# GloveControl_Module_20200316_0.net
KiCad netlist of a schematic drawn in EAGLE
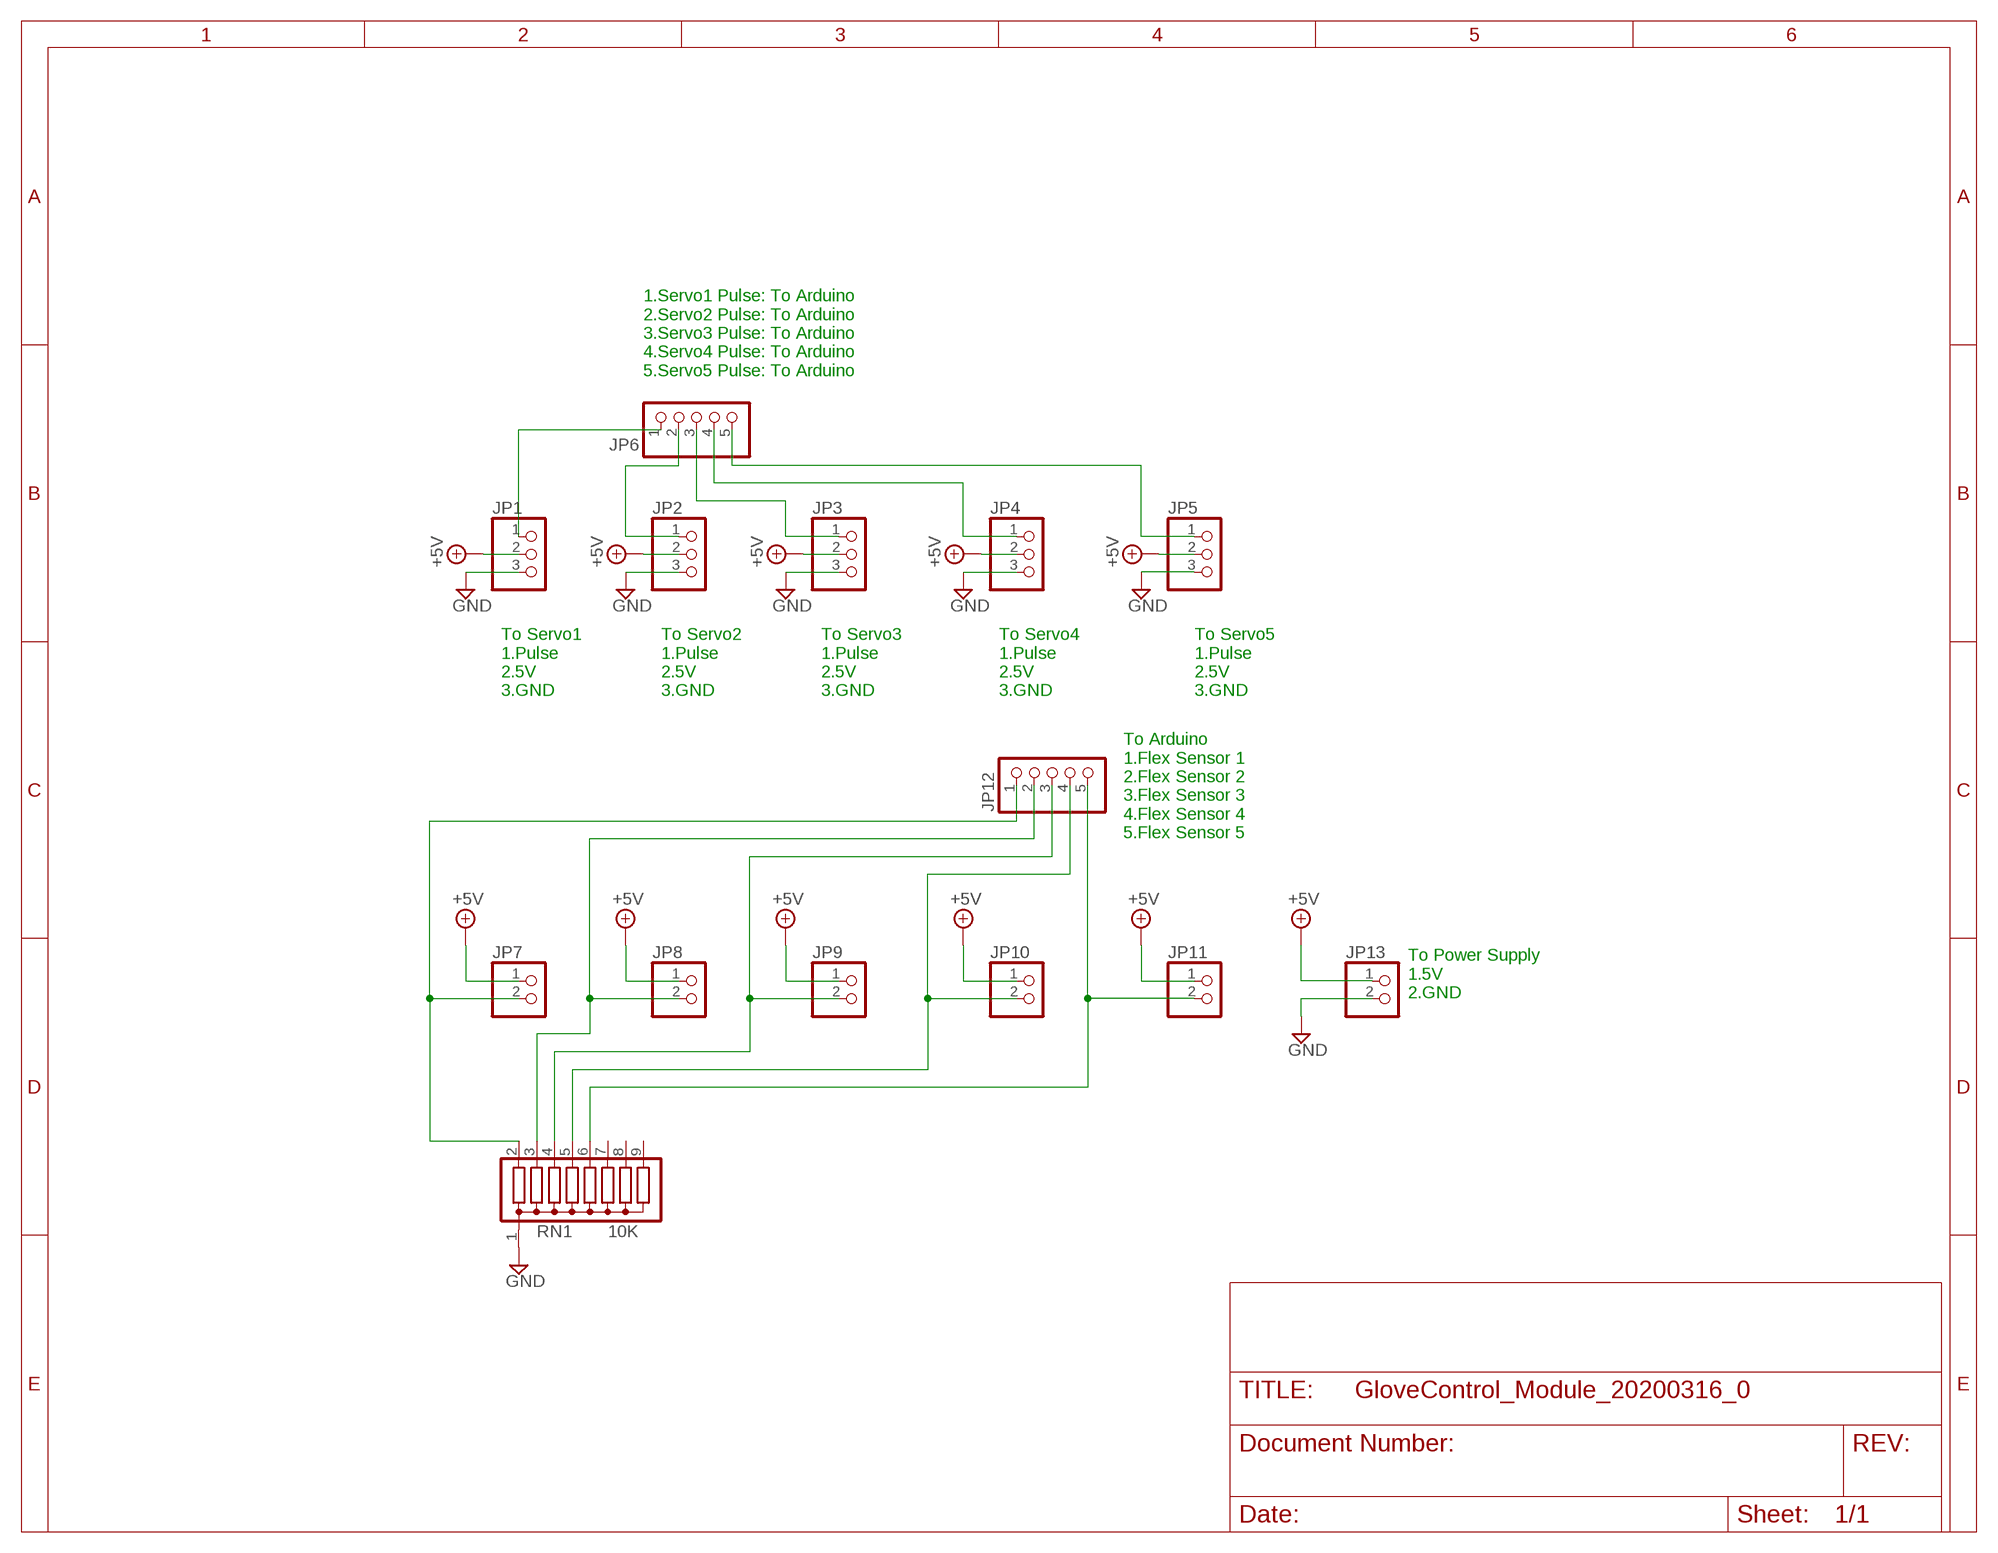
[diagram p0: schematic, sheet 1]

(export (version "E")
  (design (tool "Eeschema 10.0.6"))
  (components
    (comp (ref "JP1")
      (value "PINHD-1X3")
      (footprint "eagle-import:1X03")
      (libsource (lib "eagle-import") (part "PINHD-1X3"))
    )
    (comp (ref "JP2")
      (value "PINHD-1X3")
      (footprint "eagle-import:1X03")
      (libsource (lib "eagle-import") (part "PINHD-1X3"))
    )
    (comp (ref "JP3")
      (value "PINHD-1X3")
      (footprint "eagle-import:1X03")
      (libsource (lib "eagle-import") (part "PINHD-1X3"))
    )
    (comp (ref "JP4")
      (value "PINHD-1X3")
      (footprint "eagle-import:1X03")
      (libsource (lib "eagle-import") (part "PINHD-1X3"))
    )
    (comp (ref "JP5")
      (value "PINHD-1X3")
      (footprint "eagle-import:1X03")
      (libsource (lib "eagle-import") (part "PINHD-1X3"))
    )
    (comp (ref "JP6")
      (value "PINHD-1X5")
      (footprint "eagle-import:1X05")
      (libsource (lib "eagle-import") (part "PINHD-1X5"))
    )
    (comp (ref "JP7")
      (value "PINHD-1X2")
      (footprint "eagle-import:1X02")
      (libsource (lib "eagle-import") (part "PINHD-1X2"))
    )
    (comp (ref "JP8")
      (value "PINHD-1X2")
      (footprint "eagle-import:1X02")
      (libsource (lib "eagle-import") (part "PINHD-1X2"))
    )
    (comp (ref "JP9")
      (value "PINHD-1X2")
      (footprint "eagle-import:1X02")
      (libsource (lib "eagle-import") (part "PINHD-1X2"))
    )
    (comp (ref "JP10")
      (value "PINHD-1X2")
      (footprint "eagle-import:1X02")
      (libsource (lib "eagle-import") (part "PINHD-1X2"))
    )
    (comp (ref "JP11")
      (value "PINHD-1X2")
      (footprint "eagle-import:1X02")
      (libsource (lib "eagle-import") (part "PINHD-1X2"))
    )
    (comp (ref "JP12")
      (value "PINHD-1X5")
      (footprint "eagle-import:1X05")
      (libsource (lib "eagle-import") (part "PINHD-1X5"))
    )
    (comp (ref "JP13")
      (value "PINHD-1X2")
      (footprint "eagle-import:1X02")
      (libsource (lib "eagle-import") (part "PINHD-1X2"))
    )
    (comp (ref "RN1")
      (value "10K")
      (footprint "eagle-import:SIL9")
      (libsource (lib "eagle-import") (part "G08R"))
    )
  )
  (nets
    (net (code "1") (name "+5V") (class "Default")
      (node (ref "JP1") (pin "2") (pinfunction "2_2") (pintype "passive"))
      (node (ref "JP10") (pin "1") (pinfunction "1_1") (pintype "passive"))
      (node (ref "JP11") (pin "1") (pinfunction "1_1") (pintype "passive"))
      (node (ref "JP13") (pin "1") (pinfunction "1_1") (pintype "passive"))
      (node (ref "JP2") (pin "2") (pinfunction "2_2") (pintype "passive"))
      (node (ref "JP3") (pin "2") (pinfunction "2_2") (pintype "passive"))
      (node (ref "JP4") (pin "2") (pinfunction "2_2") (pintype "passive"))
      (node (ref "JP5") (pin "2") (pinfunction "2_2") (pintype "passive"))
      (node (ref "JP7") (pin "1") (pinfunction "1_1") (pintype "passive"))
      (node (ref "JP8") (pin "1") (pinfunction "1_1") (pintype "passive"))
      (node (ref "JP9") (pin "1") (pinfunction "1_1") (pintype "passive"))
    )
    (net (code "2") (name "GND") (class "Default")
      (node (ref "JP1") (pin "3") (pinfunction "3_3") (pintype "passive"))
      (node (ref "JP13") (pin "2") (pinfunction "2_2") (pintype "passive"))
      (node (ref "JP2") (pin "3") (pinfunction "3_3") (pintype "passive"))
      (node (ref "JP3") (pin "3") (pinfunction "3_3") (pintype "passive"))
      (node (ref "JP4") (pin "3") (pinfunction "3_3") (pintype "passive"))
      (node (ref "JP5") (pin "3") (pinfunction "3_3") (pintype "passive"))
      (node (ref "RN1") (pin "1") (pinfunction "1_1") (pintype "passive"))
    )
    (net (code "3") (name "Net-(JP1-Pad1)") (class "Default")
      (node (ref "JP1") (pin "1") (pinfunction "1_1") (pintype "passive"))
      (node (ref "JP6") (pin "1") (pinfunction "1_1") (pintype "passive"))
    )
    (net (code "4") (name "Net-(JP2-Pad1)") (class "Default")
      (node (ref "JP2") (pin "1") (pinfunction "1_1") (pintype "passive"))
      (node (ref "JP6") (pin "2") (pinfunction "2_2") (pintype "passive"))
    )
    (net (code "5") (name "Net-(JP3-Pad1)") (class "Default")
      (node (ref "JP3") (pin "1") (pinfunction "1_1") (pintype "passive"))
      (node (ref "JP6") (pin "3") (pinfunction "3_3") (pintype "passive"))
    )
    (net (code "6") (name "Net-(JP4-Pad1)") (class "Default")
      (node (ref "JP4") (pin "1") (pinfunction "1_1") (pintype "passive"))
      (node (ref "JP6") (pin "4") (pinfunction "4_4") (pintype "passive"))
    )
    (net (code "7") (name "Net-(JP5-Pad1)") (class "Default")
      (node (ref "JP5") (pin "1") (pinfunction "1_1") (pintype "passive"))
      (node (ref "JP6") (pin "5") (pinfunction "5_5") (pintype "passive"))
    )
    (net (code "8") (name "Net-(JP10-Pad2)") (class "Default")
      (node (ref "JP10") (pin "2") (pinfunction "2_2") (pintype "passive"))
      (node (ref "JP12") (pin "4") (pinfunction "4_4") (pintype "passive"))
      (node (ref "RN1") (pin "5") (pinfunction "5_5") (pintype "passive"))
    )
    (net (code "9") (name "Net-(JP11-Pad2)") (class "Default")
      (node (ref "JP11") (pin "2") (pinfunction "2_2") (pintype "passive"))
      (node (ref "JP12") (pin "5") (pinfunction "5_5") (pintype "passive"))
      (node (ref "RN1") (pin "6") (pinfunction "6_6") (pintype "passive"))
    )
    (net (code "10") (name "Net-(JP12-Pad1)") (class "Default")
      (node (ref "JP12") (pin "1") (pinfunction "1_1") (pintype "passive"))
      (node (ref "JP7") (pin "2") (pinfunction "2_2") (pintype "passive"))
      (node (ref "RN1") (pin "2") (pinfunction "2_2") (pintype "passive"))
    )
    (net (code "11") (name "Net-(JP12-Pad2)") (class "Default")
      (node (ref "JP12") (pin "2") (pinfunction "2_2") (pintype "passive"))
      (node (ref "JP8") (pin "2") (pinfunction "2_2") (pintype "passive"))
      (node (ref "RN1") (pin "3") (pinfunction "3_3") (pintype "passive"))
    )
    (net (code "12") (name "Net-(JP12-Pad3)") (class "Default")
      (node (ref "JP12") (pin "3") (pinfunction "3_3") (pintype "passive"))
      (node (ref "JP9") (pin "2") (pinfunction "2_2") (pintype "passive"))
      (node (ref "RN1") (pin "4") (pinfunction "4_4") (pintype "passive"))
    )
    (net (code "13") (name "unconnected-(RN1-Pad7)") (class "Default")
      (node (ref "RN1") (pin "7") (pinfunction "7_7") (pintype "passive"))
    )
    (net (code "14") (name "unconnected-(RN1-Pad8)") (class "Default")
      (node (ref "RN1") (pin "8") (pinfunction "8_8") (pintype "passive"))
    )
    (net (code "15") (name "unconnected-(RN1-Pad9)") (class "Default")
      (node (ref "RN1") (pin "9") (pinfunction "9_9") (pintype "passive"))
    )
  )
)
